# Pupitre.net
KiCad netlist of a schematic drawn in EAGLE
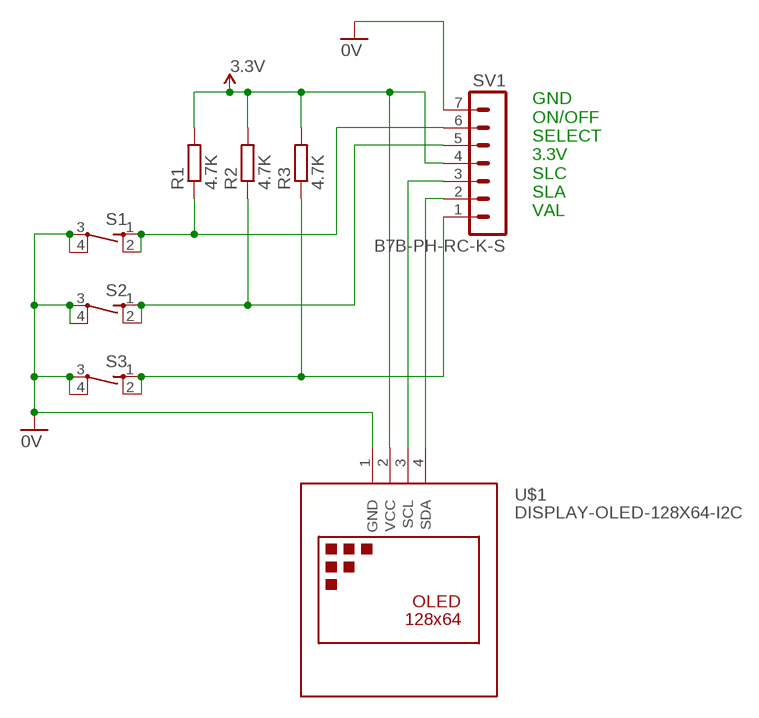
[diagram p0: schematic, sheet 1]

(export (version "E")
  (design (tool "Eeschema 10.0.6"))
  (components
    (comp (ref "R1")
      (value "4.7K")
      (footprint "eagle-import:0207_10")
      (libsource (lib "eagle-import") (part "R-EU_0207/10"))
    )
    (comp (ref "R2")
      (value "4.7K")
      (footprint "eagle-import:0207_10")
      (libsource (lib "eagle-import") (part "R-EU_0207/10"))
    )
    (comp (ref "R3")
      (value "4.7K")
      (footprint "eagle-import:0207_10")
      (libsource (lib "eagle-import") (part "R-EU_0207/10"))
    )
    (comp (ref "S1")
      (value "SWITCH_10-XX")
      (footprint "eagle-import:SWITCH-10XX")
      (libsource (lib "eagle-import") (part "SWITCH_10-XX"))
    )
    (comp (ref "S2")
      (value "SWITCH_10-XX")
      (footprint "eagle-import:SWITCH-10XX")
      (libsource (lib "eagle-import") (part "SWITCH_10-XX"))
    )
    (comp (ref "S3")
      (value "SWITCH_10-XX")
      (footprint "eagle-import:SWITCH-10XX")
      (libsource (lib "eagle-import") (part "SWITCH_10-XX"))
    )
    (comp (ref "SV1")
      (value "B7B-PH-RC-K-S")
      (footprint "eagle-import:B7B-PH-K-S")
      (libsource (lib "eagle-import") (part "B7B-PH-RC-K-S"))
    )
    (comp (ref "U$1")
      (value "DISPLAY-OLED-128X64-I2C")
      (footprint "eagle-import:DISPLAY-OLED-128X64-I2C")
      (libsource (lib "eagle-import") (part "DISPLAY-OLED-128X64-I2C"))
    )
  )
  (nets
    (net (code "1") (name "0V") (class "Default")
      (node (ref "S1") (pin "3") (pinfunction "P_3") (pintype "passive"))
      (node (ref "S1") (pin "4") (pinfunction "P1_4") (pintype "passive"))
      (node (ref "S2") (pin "3") (pinfunction "P_3") (pintype "passive"))
      (node (ref "S2") (pin "4") (pinfunction "P1_4") (pintype "passive"))
      (node (ref "S3") (pin "3") (pinfunction "P_3") (pintype "passive"))
      (node (ref "S3") (pin "4") (pinfunction "P1_4") (pintype "passive"))
      (node (ref "SV1") (pin "7") (pinfunction "7_7") (pintype "passive"))
      (node (ref "U$1") (pin "1") (pinfunction "GND_1") (pintype "power_in"))
    )
    (net (code "2") (name "3.3V") (class "Default")
      (node (ref "R1") (pin "2") (pinfunction "2_2") (pintype "passive"))
      (node (ref "R2") (pin "2") (pinfunction "2_2") (pintype "passive"))
      (node (ref "R3") (pin "2") (pinfunction "2_2") (pintype "passive"))
      (node (ref "SV1") (pin "4") (pinfunction "4_4") (pintype "passive"))
      (node (ref "U$1") (pin "2") (pinfunction "VCC_2") (pintype "power_in"))
    )
    (net (code "3") (name "Net-(S1-S)") (class "Default")
      (node (ref "R1") (pin "1") (pinfunction "1_1") (pintype "passive"))
      (node (ref "S1") (pin "1") (pinfunction "S_1") (pintype "passive"))
      (node (ref "S1") (pin "2") (pinfunction "S1_2") (pintype "passive"))
      (node (ref "SV1") (pin "6") (pinfunction "6_6") (pintype "passive"))
    )
    (net (code "4") (name "Net-(S2-S)") (class "Default")
      (node (ref "R2") (pin "1") (pinfunction "1_1") (pintype "passive"))
      (node (ref "S2") (pin "1") (pinfunction "S_1") (pintype "passive"))
      (node (ref "S2") (pin "2") (pinfunction "S1_2") (pintype "passive"))
      (node (ref "SV1") (pin "5") (pinfunction "5_5") (pintype "passive"))
    )
    (net (code "5") (name "Net-(S3-S)") (class "Default")
      (node (ref "R3") (pin "1") (pinfunction "1_1") (pintype "passive"))
      (node (ref "S3") (pin "1") (pinfunction "S_1") (pintype "passive"))
      (node (ref "S3") (pin "2") (pinfunction "S1_2") (pintype "passive"))
      (node (ref "SV1") (pin "1") (pinfunction "1_1") (pintype "passive"))
    )
    (net (code "6") (name "Net-(U$1-SCL)") (class "Default")
      (node (ref "SV1") (pin "3") (pinfunction "3_3") (pintype "passive"))
      (node (ref "U$1") (pin "3") (pinfunction "SCL_3") (pintype "bidirectional"))
    )
    (net (code "7") (name "Net-(U$1-SDA)") (class "Default")
      (node (ref "SV1") (pin "2") (pinfunction "2_2") (pintype "passive"))
      (node (ref "U$1") (pin "4") (pinfunction "SDA_4") (pintype "bidirectional"))
    )
  )
)
